# 246_PWM_PCA9685.net
KiCad netlist of a schematic drawn in EAGLE
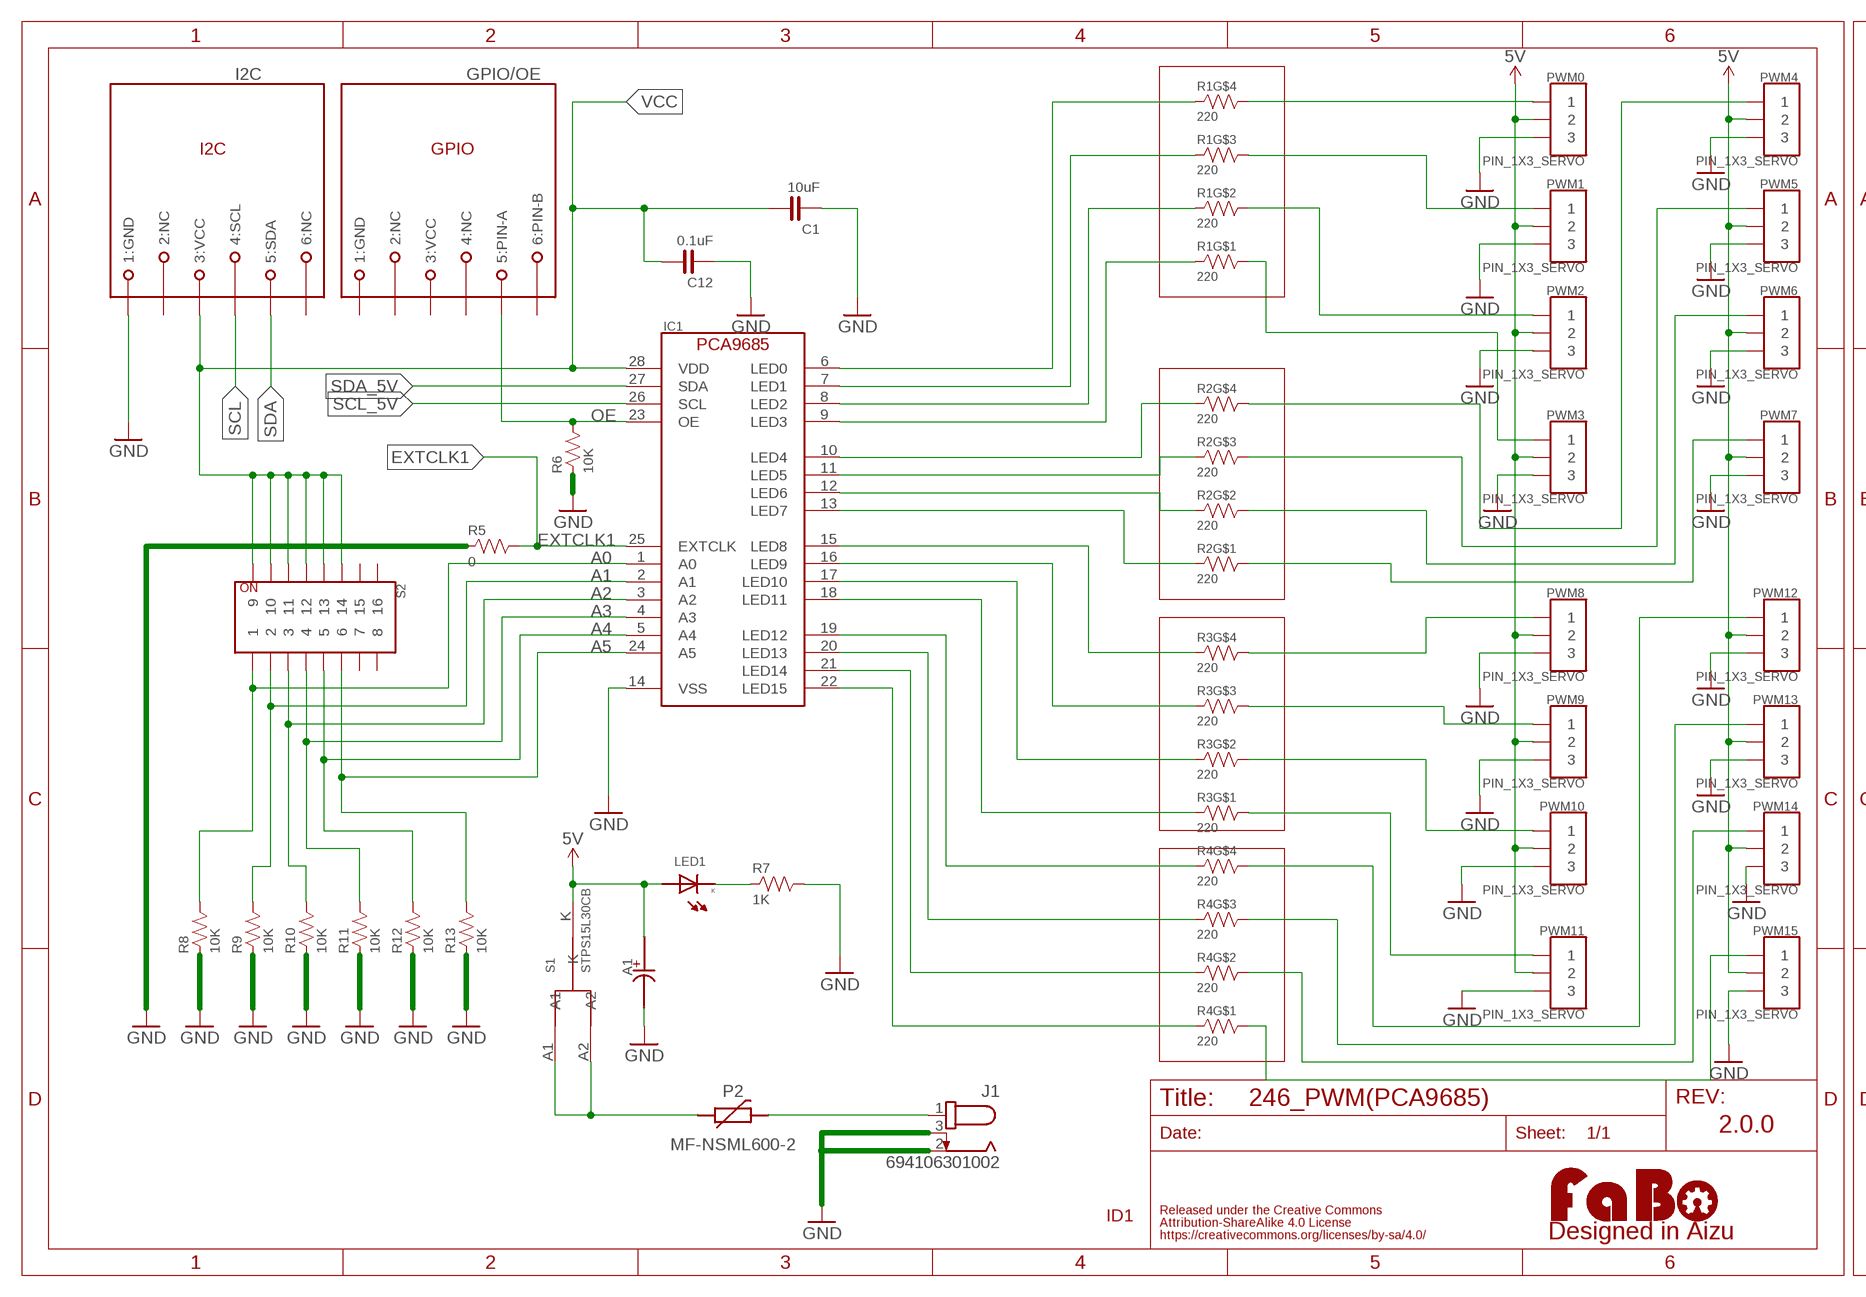
[diagram p0: schematic, sheet 1, part 1 of 2]
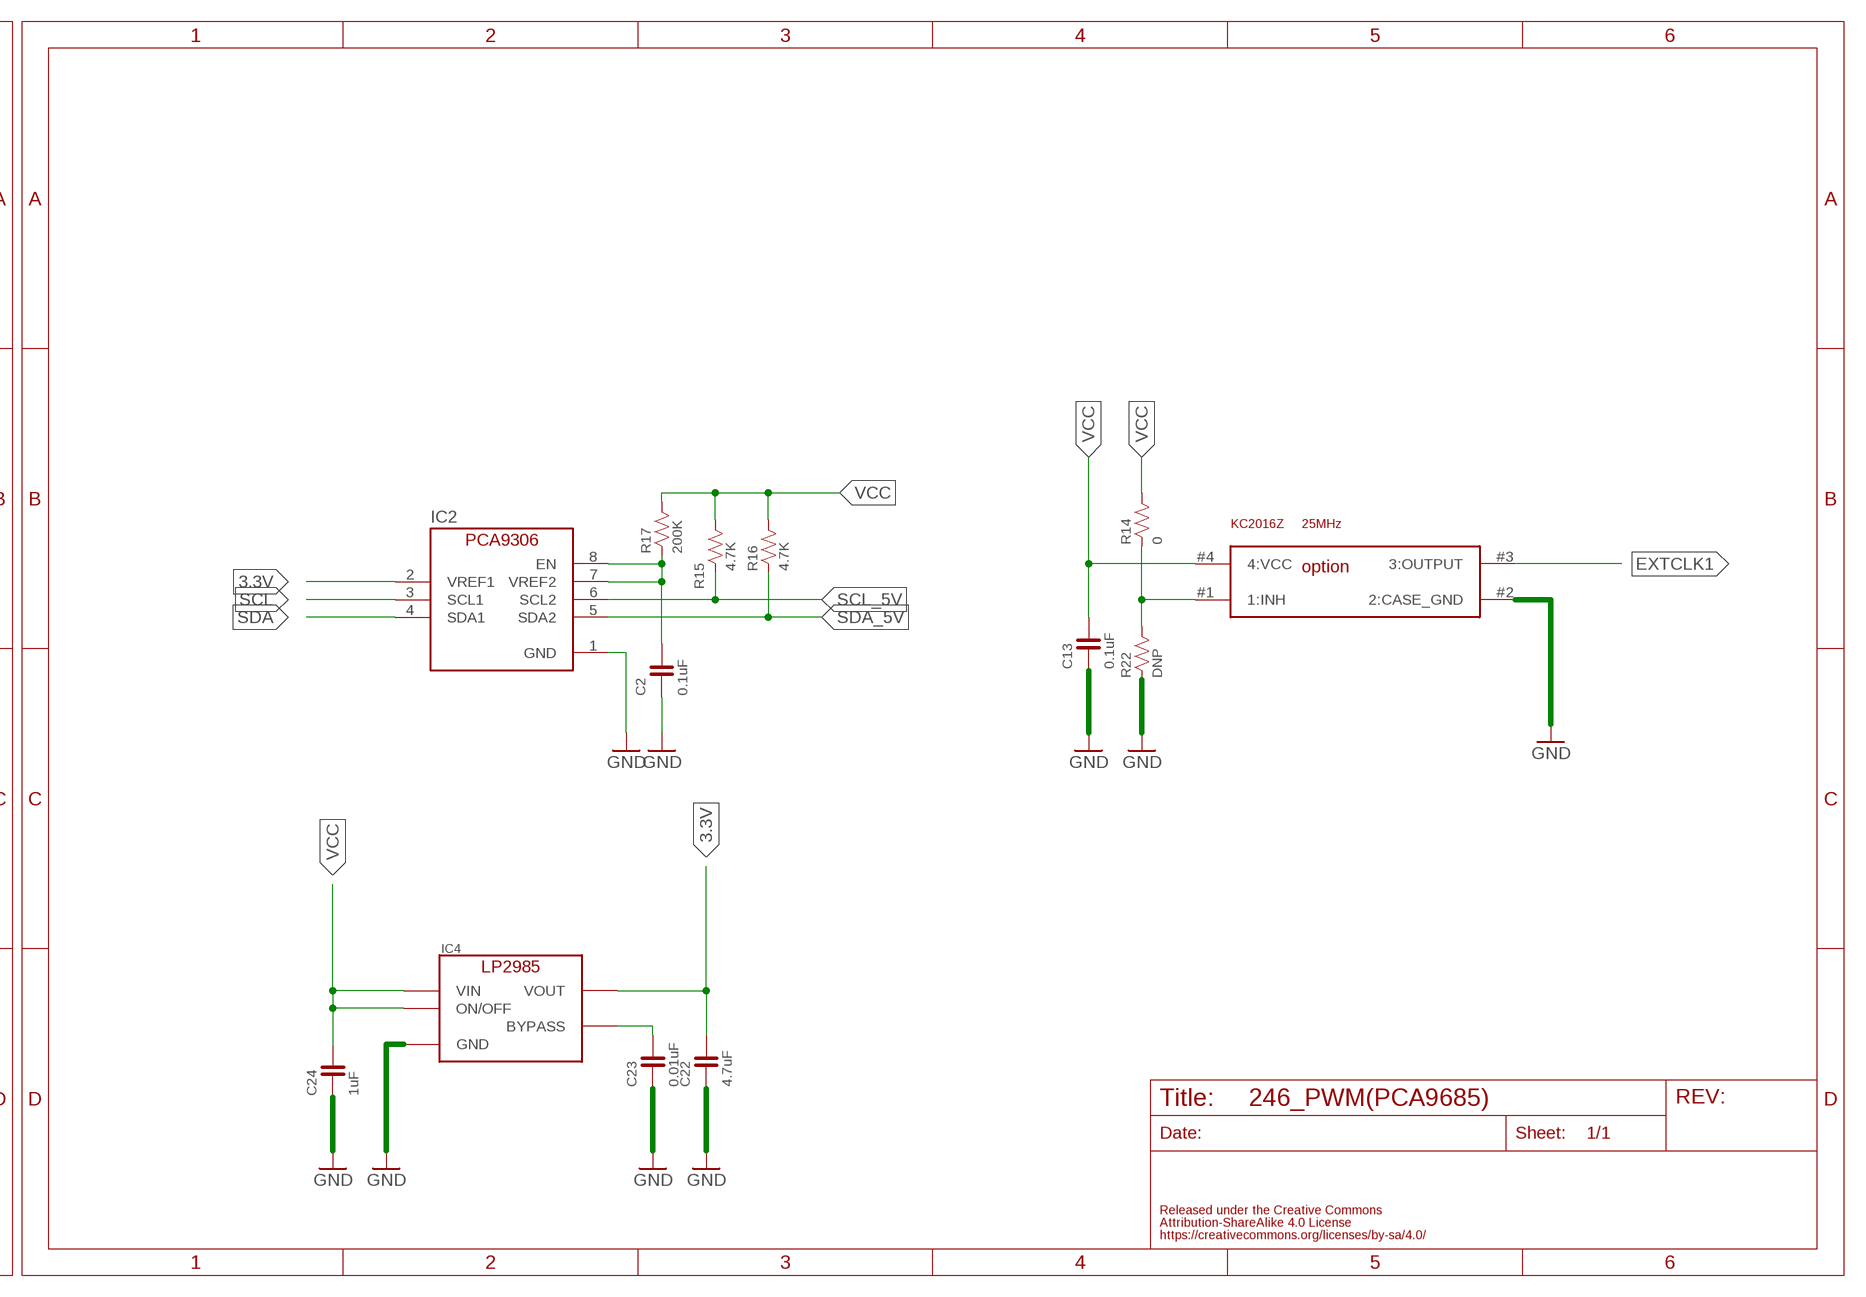
[diagram p1: schematic, sheet 1, part 2 of 2]

(export (version "E")
  (design (tool "Eeschema 10.0.6"))
  (components
    (comp (ref "A1")
      (value "CAPACITOR-OS-CON")
      (footprint "eagle-import:F13")
      (libsource (lib "eagle-import") (part "CAPACITOR-OS-CON"))
    )
    (comp (ref "C1")
      (value "10uF")
      (footprint "eagle-import:0603")
      (libsource (lib "eagle-import") (part "CAPACITOR-0603"))
    )
    (comp (ref "C2")
      (value "0.1uF")
      (footprint "eagle-import:0402")
      (libsource (lib "eagle-import") (part "CAPACITOR-0402"))
    )
    (comp (ref "C12")
      (value "0.1uF")
      (footprint "eagle-import:0603")
      (libsource (lib "eagle-import") (part "CAPACITOR-0603"))
    )
    (comp (ref "C13")
      (value "0.1uF")
      (footprint "eagle-import:0402")
      (libsource (lib "eagle-import") (part "CAPACITOR-0402"))
    )
    (comp (ref "C22")
      (value "4.7uF")
      (footprint "eagle-import:0603")
      (libsource (lib "eagle-import") (part "CAPACITOR-0603"))
    )
    (comp (ref "C23")
      (value "0.01uF")
      (footprint "eagle-import:0603")
      (libsource (lib "eagle-import") (part "CAPACITOR-0603"))
    )
    (comp (ref "C24")
      (value "1uF")
      (footprint "eagle-import:0603")
      (libsource (lib "eagle-import") (part "CAPACITOR-0603"))
    )
    (comp (ref "GPIO/OE")
      (value "MODULAR-JACK-6P-RJ11_GPIO")
      (footprint "eagle-import:7002-6PXC-X")
      (libsource (lib "eagle-import") (part "MODULAR-JACK-6P-RJ11_GPIO"))
    )
    (comp (ref "I2C")
      (value "MODULAR-JACK-6P-RJ11_I2C")
      (footprint "eagle-import:7002-6PXC-X")
      (libsource (lib "eagle-import") (part "MODULAR-JACK-6P-RJ11_I2C"))
    )
    (comp (ref "IC1")
      (value "PCA9685BS")
      (footprint "eagle-import:PCA9685")
      (libsource (lib "eagle-import") (part "PCA9685BS"))
    )
    (comp (ref "IC2")
      (value "PCA9306_GM")
      (footprint "eagle-import:XQFN8")
      (libsource (lib "eagle-import") (part "PCA9306_GM"))
    )
    (comp (ref "IC4")
      (value "LP2985-33DBV")
      (footprint "eagle-import:SOT-23-5")
      (libsource (lib "eagle-import") (part "LP2985-33DBV"))
    )
    (comp (ref "J1")
      (value "694106301002")
      (footprint "eagle-import:694106301002")
      (fields
        (field (name "DIGIKEY_PART_NUMBER") "732-5930-ND")
        (field (name "MANUFACTURER") "Wurth Electronics Inc.")
        (field (name "CREATED_BY") "PCBLayout.com")
      )
      (libsource (lib "eagle-import") (part "694106301002"))
    )
    (comp (ref "LED1")
      (value "LED-0603")
      (footprint "eagle-import:0603")
      (libsource (lib "eagle-import") (part "LED-0603"))
    )
    (comp (ref "LOGO1")
      (value "LOGO_FABO-M_BOTTOM")
      (footprint "eagle-import:LOGO_FABO_M_BOTTOM")
      (libsource (lib "eagle-import") (part "LOGO_FABO-M_BOTTOM"))
    )
    (comp (ref "P2")
      (value "MF-NSML600-2")
      (footprint "eagle-import:1206")
      (libsource (lib "eagle-import") (part "POLYSWITCH1206"))
    )
    (comp (ref "PWM0")
      (value "PIN_1X3_SERVO")
      (footprint "eagle-import:PIN_1X3_NOLABEL_PWM")
      (libsource (lib "eagle-import") (part "PIN_1X3_SERVO"))
    )
    (comp (ref "PWM1")
      (value "PIN_1X3_SERVO")
      (footprint "eagle-import:PIN_1X3_NOLABEL_PWM")
      (libsource (lib "eagle-import") (part "PIN_1X3_SERVO"))
    )
    (comp (ref "PWM2")
      (value "PIN_1X3_SERVO")
      (footprint "eagle-import:PIN_1X3_NOLABEL_PWM")
      (libsource (lib "eagle-import") (part "PIN_1X3_SERVO"))
    )
    (comp (ref "PWM3")
      (value "PIN_1X3_SERVO")
      (footprint "eagle-import:PIN_1X3_NOLABEL_PWM")
      (libsource (lib "eagle-import") (part "PIN_1X3_SERVO"))
    )
    (comp (ref "PWM4")
      (value "PIN_1X3_SERVO")
      (footprint "eagle-import:PIN_1X3_NOLABEL_PWM")
      (libsource (lib "eagle-import") (part "PIN_1X3_SERVO"))
    )
    (comp (ref "PWM5")
      (value "PIN_1X3_SERVO")
      (footprint "eagle-import:PIN_1X3_NOLABEL_PWM")
      (libsource (lib "eagle-import") (part "PIN_1X3_SERVO"))
    )
    (comp (ref "PWM6")
      (value "PIN_1X3_SERVO")
      (footprint "eagle-import:PIN_1X3_NOLABEL_PWM")
      (libsource (lib "eagle-import") (part "PIN_1X3_SERVO"))
    )
    (comp (ref "PWM7")
      (value "PIN_1X3_SERVO")
      (footprint "eagle-import:PIN_1X3_NOLABEL_PWM")
      (libsource (lib "eagle-import") (part "PIN_1X3_SERVO"))
    )
    (comp (ref "PWM8")
      (value "PIN_1X3_SERVO")
      (footprint "eagle-import:PIN_1X3_NOLABEL_PWM")
      (libsource (lib "eagle-import") (part "PIN_1X3_SERVO"))
    )
    (comp (ref "PWM9")
      (value "PIN_1X3_SERVO")
      (footprint "eagle-import:PIN_1X3_NOLABEL_PWM")
      (libsource (lib "eagle-import") (part "PIN_1X3_SERVO"))
    )
    (comp (ref "PWM10")
      (value "PIN_1X3_SERVO")
      (footprint "eagle-import:PIN_1X3_NOLABEL_PWM")
      (libsource (lib "eagle-import") (part "PIN_1X3_SERVO"))
    )
    (comp (ref "PWM11")
      (value "PIN_1X3_SERVO")
      (footprint "eagle-import:PIN_1X3_NOLABEL_PWM")
      (libsource (lib "eagle-import") (part "PIN_1X3_SERVO"))
    )
    (comp (ref "PWM12")
      (value "PIN_1X3_SERVO")
      (footprint "eagle-import:PIN_1X3_NOLABEL_PWM")
      (libsource (lib "eagle-import") (part "PIN_1X3_SERVO"))
    )
    (comp (ref "PWM13")
      (value "PIN_1X3_SERVO")
      (footprint "eagle-import:PIN_1X3_NOLABEL_PWM")
      (libsource (lib "eagle-import") (part "PIN_1X3_SERVO"))
    )
    (comp (ref "PWM14")
      (value "PIN_1X3_SERVO")
      (footprint "eagle-import:PIN_1X3_NOLABEL_PWM")
      (libsource (lib "eagle-import") (part "PIN_1X3_SERVO"))
    )
    (comp (ref "PWM15")
      (value "PIN_1X3_SERVO")
      (footprint "eagle-import:PIN_1X3_NOLABEL_PWM")
      (libsource (lib "eagle-import") (part "PIN_1X3_SERVO"))
    )
    (comp (ref "R1")
      (value "220")
      (footprint "eagle-import:EXBV8V")
      (libsource (lib "eagle-import") (part "RESISTOR_ARRAY"))
    )
    (comp (ref "R2")
      (value "220")
      (footprint "eagle-import:EXBV8V")
      (libsource (lib "eagle-import") (part "RESISTOR_ARRAY"))
    )
    (comp (ref "R3")
      (value "220")
      (footprint "eagle-import:EXBV8V")
      (libsource (lib "eagle-import") (part "RESISTOR_ARRAY"))
    )
    (comp (ref "R4")
      (value "220")
      (footprint "eagle-import:EXBV8V")
      (libsource (lib "eagle-import") (part "RESISTOR_ARRAY"))
    )
    (comp (ref "R5")
      (value "0")
      (footprint "eagle-import:0603")
      (libsource (lib "eagle-import") (part "RESISTOR-0603"))
    )
    (comp (ref "R6")
      (value "10K")
      (footprint "eagle-import:0603")
      (libsource (lib "eagle-import") (part "RESISTOR-0603"))
    )
    (comp (ref "R7")
      (value "1K")
      (footprint "eagle-import:0603")
      (libsource (lib "eagle-import") (part "RESISTOR-0603"))
    )
    (comp (ref "R8")
      (value "10K")
      (footprint "eagle-import:0603")
      (libsource (lib "eagle-import") (part "RESISTOR-0603"))
    )
    (comp (ref "R9")
      (value "10K")
      (footprint "eagle-import:0603")
      (libsource (lib "eagle-import") (part "RESISTOR-0603"))
    )
    (comp (ref "R10")
      (value "10K")
      (footprint "eagle-import:0603")
      (libsource (lib "eagle-import") (part "RESISTOR-0603"))
    )
    (comp (ref "R11")
      (value "10K")
      (footprint "eagle-import:0603")
      (libsource (lib "eagle-import") (part "RESISTOR-0603"))
    )
    (comp (ref "R12")
      (value "10K")
      (footprint "eagle-import:0603")
      (libsource (lib "eagle-import") (part "RESISTOR-0603"))
    )
    (comp (ref "R13")
      (value "10K")
      (footprint "eagle-import:0603")
      (libsource (lib "eagle-import") (part "RESISTOR-0603"))
    )
    (comp (ref "R14")
      (value "0")
      (footprint "eagle-import:0402")
      (libsource (lib "eagle-import") (part "RESISTOR-0402"))
    )
    (comp (ref "R15")
      (value "4.7K")
      (footprint "eagle-import:0402")
      (libsource (lib "eagle-import") (part "RESISTOR-0402"))
    )
    (comp (ref "R16")
      (value "4.7K")
      (footprint "eagle-import:0402")
      (libsource (lib "eagle-import") (part "RESISTOR-0402"))
    )
    (comp (ref "R17")
      (value "200K")
      (footprint "eagle-import:0402")
      (libsource (lib "eagle-import") (part "RESISTOR-0402"))
    )
    (comp (ref "R22")
      (value "DNP")
      (footprint "eagle-import:0402")
      (libsource (lib "eagle-import") (part "RESISTOR-0402"))
    )
    (comp (ref "S1")
      (value "STPS15L30CB")
      (footprint "eagle-import:STPS15L30C")
      (libsource (lib "eagle-import") (part "STPS15L30C"))
    )
    (comp (ref "S2")
      (value "KHS82")
      (footprint "eagle-import:KHS82")
      (libsource (lib "eagle-import") (part "KHS82"))
    )
    (comp (ref "U$11")
      (value "KC2016Z")
      (footprint "eagle-import:KC2016Z")
      (libsource (lib "eagle-import") (part "KC2016Z"))
    )
  )
  (nets
    (net (code "1") (name "/1:GND") (class "Default")
      (node (ref "GPIO/OE") (pin "1") (pinfunction "1:GND_1") (pintype "power_in"))
    )
    (net (code "2") (name "/3:VCC") (class "Default")
      (node (ref "GPIO/OE") (pin "3") (pinfunction "3:VCC_3") (pintype "power_in"))
    )
    (net (code "3") (name "/A0") (class "Default")
      (node (ref "IC1") (pin "1") (pinfunction "A0_1") (pintype "bidirectional"))
      (node (ref "R8") (pin "2") (pinfunction "2_2") (pintype "bidirectional"))
      (node (ref "S2") (pin "1") (pinfunction "1_1") (pintype "input"))
    )
    (net (code "4") (name "/A1") (class "Default")
      (node (ref "IC1") (pin "2") (pinfunction "A1_2") (pintype "bidirectional"))
      (node (ref "R9") (pin "2") (pinfunction "2_2") (pintype "bidirectional"))
      (node (ref "S2") (pin "2") (pinfunction "2_2") (pintype "input"))
    )
    (net (code "5") (name "/A2") (class "Default")
      (node (ref "IC1") (pin "3") (pinfunction "A2_3") (pintype "bidirectional"))
      (node (ref "R10") (pin "2") (pinfunction "2_2") (pintype "bidirectional"))
      (node (ref "S2") (pin "3") (pinfunction "3_3") (pintype "input"))
    )
    (net (code "6") (name "/A3") (class "Default")
      (node (ref "IC1") (pin "4") (pinfunction "A3_4") (pintype "bidirectional"))
      (node (ref "R11") (pin "2") (pinfunction "2_2") (pintype "bidirectional"))
      (node (ref "S2") (pin "4") (pinfunction "4_4") (pintype "input"))
    )
    (net (code "7") (name "/A4") (class "Default")
      (node (ref "IC1") (pin "5") (pinfunction "A4_5") (pintype "bidirectional"))
      (node (ref "R12") (pin "2") (pinfunction "2_2") (pintype "bidirectional"))
      (node (ref "S2") (pin "5") (pinfunction "5_5") (pintype "input"))
    )
    (net (code "8") (name "/A5") (class "Default")
      (node (ref "IC1") (pin "24") (pinfunction "A5_24") (pintype "bidirectional"))
      (node (ref "R13") (pin "2") (pinfunction "2_2") (pintype "bidirectional"))
      (node (ref "S2") (pin "6") (pinfunction "6_6") (pintype "input"))
    )
    (net (code "9") (name "/OE") (class "Default")
      (node (ref "GPIO/OE") (pin "5") (pinfunction "5:PIN-A_5") (pintype "bidirectional"))
      (node (ref "IC1") (pin "23") (pinfunction "OE_23") (pintype "bidirectional"))
      (node (ref "R6") (pin "2") (pinfunction "2_2") (pintype "bidirectional"))
    )
    (net (code "10") (name "3.3V") (class "Default")
      (node (ref "C22") (pin "2") (pinfunction "2_2") (pintype "passive"))
      (node (ref "IC2") (pin "2") (pinfunction "VREF1_2") (pintype "bidirectional"))
      (node (ref "IC4") (pin "5") (pinfunction "VOUT_5") (pintype "output"))
    )
    (net (code "11") (name "5V") (class "Default")
      (node (ref "A1") (pin "ANODE") (pinfunction "+_ANODE") (pintype "passive"))
      (node (ref "LED1") (pin "ANODE") (pinfunction "ANODE_ANODE") (pintype "passive"))
      (node (ref "PWM0") (pin "2:VCC") (pinfunction "2_2:VCC") (pintype "bidirectional"))
      (node (ref "PWM1") (pin "2:VCC") (pinfunction "2_2:VCC") (pintype "bidirectional"))
      (node (ref "PWM10") (pin "2:VCC") (pinfunction "2_2:VCC") (pintype "bidirectional"))
      (node (ref "PWM11") (pin "2:VCC") (pinfunction "2_2:VCC") (pintype "bidirectional"))
      (node (ref "PWM12") (pin "2:VCC") (pinfunction "2_2:VCC") (pintype "bidirectional"))
      (node (ref "PWM13") (pin "2:VCC") (pinfunction "2_2:VCC") (pintype "bidirectional"))
      (node (ref "PWM14") (pin "2:VCC") (pinfunction "2_2:VCC") (pintype "bidirectional"))
      (node (ref "PWM15") (pin "2:VCC") (pinfunction "2_2:VCC") (pintype "bidirectional"))
      (node (ref "PWM2") (pin "2:VCC") (pinfunction "2_2:VCC") (pintype "bidirectional"))
      (node (ref "PWM3") (pin "2:VCC") (pinfunction "2_2:VCC") (pintype "bidirectional"))
      (node (ref "PWM4") (pin "2:VCC") (pinfunction "2_2:VCC") (pintype "bidirectional"))
      (node (ref "PWM5") (pin "2:VCC") (pinfunction "2_2:VCC") (pintype "bidirectional"))
      (node (ref "PWM6") (pin "2:VCC") (pinfunction "2_2:VCC") (pintype "bidirectional"))
      (node (ref "PWM7") (pin "2:VCC") (pinfunction "2_2:VCC") (pintype "bidirectional"))
      (node (ref "PWM8") (pin "2:VCC") (pinfunction "2_2:VCC") (pintype "bidirectional"))
      (node (ref "PWM9") (pin "2:VCC") (pinfunction "2_2:VCC") (pintype "bidirectional"))
      (node (ref "S1") (pin "K") (pinfunction "K_K") (pintype "bidirectional"))
    )
    (net (code "12") (name "EXTCLK1") (class "Default")
      (node (ref "IC1") (pin "25") (pinfunction "EXTCLK_25") (pintype "bidirectional"))
      (node (ref "R5") (pin "2") (pinfunction "2_2") (pintype "bidirectional"))
      (node (ref "U$11") (pin "#3") (pinfunction "3:OUTPUT_#3") (pintype "bidirectional"))
    )
    (net (code "13") (name "GND") (class "Default")
      (node (ref "A1") (pin "CATHODE") (pinfunction "-_CATHODE") (pintype "passive"))
      (node (ref "C1") (pin "1") (pinfunction "1_1") (pintype "passive"))
      (node (ref "C12") (pin "1") (pinfunction "1_1") (pintype "passive"))
      (node (ref "C13") (pin "P$1") (pinfunction "1_P$1") (pintype "passive"))
      (node (ref "C2") (pin "P$1") (pinfunction "1_P$1") (pintype "passive"))
      (node (ref "C22") (pin "1") (pinfunction "1_1") (pintype "passive"))
      (node (ref "C23") (pin "1") (pinfunction "1_1") (pintype "passive"))
      (node (ref "C24") (pin "1") (pinfunction "1_1") (pintype "passive"))
      (node (ref "I2C") (pin "1") (pinfunction "1:GND_1") (pintype "power_in"))
      (node (ref "IC1") (pin "14") (pinfunction "VSS_14") (pintype "bidirectional"))
      (node (ref "IC2") (pin "1") (pinfunction "GND_1") (pintype "bidirectional"))
      (node (ref "IC4") (pin "2") (pinfunction "GND_2") (pintype "power_in"))
      (node (ref "J1") (pin "2") (pinfunction "2_2") (pintype "passive"))
      (node (ref "J1") (pin "3") (pinfunction "3_3") (pintype "passive"))
      (node (ref "PWM0") (pin "3:GND") (pinfunction "3_3:GND") (pintype "bidirectional"))
      (node (ref "PWM1") (pin "3:GND") (pinfunction "3_3:GND") (pintype "bidirectional"))
      (node (ref "PWM10") (pin "3:GND") (pinfunction "3_3:GND") (pintype "bidirectional"))
      (node (ref "PWM11") (pin "3:GND") (pinfunction "3_3:GND") (pintype "bidirectional"))
      (node (ref "PWM12") (pin "3:GND") (pinfunction "3_3:GND") (pintype "bidirectional"))
      (node (ref "PWM13") (pin "3:GND") (pinfunction "3_3:GND") (pintype "bidirectional"))
      (node (ref "PWM14") (pin "3:GND") (pinfunction "3_3:GND") (pintype "bidirectional"))
      (node (ref "PWM15") (pin "3:GND") (pinfunction "3_3:GND") (pintype "bidirectional"))
      (node (ref "PWM2") (pin "3:GND") (pinfunction "3_3:GND") (pintype "bidirectional"))
      (node (ref "PWM3") (pin "3:GND") (pinfunction "3_3:GND") (pintype "bidirectional"))
      (node (ref "PWM4") (pin "3:GND") (pinfunction "3_3:GND") (pintype "bidirectional"))
      (node (ref "PWM5") (pin "3:GND") (pinfunction "3_3:GND") (pintype "bidirectional"))
      (node (ref "PWM6") (pin "3:GND") (pinfunction "3_3:GND") (pintype "bidirectional"))
      (node (ref "PWM7") (pin "3:GND") (pinfunction "3_3:GND") (pintype "bidirectional"))
      (node (ref "PWM8") (pin "3:GND") (pinfunction "3_3:GND") (pintype "bidirectional"))
      (node (ref "PWM9") (pin "3:GND") (pinfunction "3_3:GND") (pintype "bidirectional"))
      (node (ref "R10") (pin "1") (pinfunction "1_1") (pintype "bidirectional"))
      (node (ref "R11") (pin "1") (pinfunction "1_1") (pintype "bidirectional"))
      (node (ref "R12") (pin "1") (pinfunction "1_1") (pintype "bidirectional"))
      (node (ref "R13") (pin "1") (pinfunction "1_1") (pintype "bidirectional"))
      (node (ref "R22") (pin "P$1") (pinfunction "1_P$1") (pintype "bidirectional"))
      (node (ref "R5") (pin "1") (pinfunction "1_1") (pintype "bidirectional"))
      (node (ref "R6") (pin "1") (pinfunction "1_1") (pintype "bidirectional"))
      (node (ref "R7") (pin "2") (pinfunction "2_2") (pintype "bidirectional"))
      (node (ref "R8") (pin "1") (pinfunction "1_1") (pintype "bidirectional"))
      (node (ref "R9") (pin "1") (pinfunction "1_1") (pintype "bidirectional"))
      (node (ref "U$11") (pin "#2") (pinfunction "2:CASE_GND_#2") (pintype "bidirectional"))
    )
    (net (code "14") (name "Net-(C2-2)") (class "Default")
      (node (ref "C2") (pin "P$2") (pinfunction "2_P$2") (pintype "passive"))
      (node (ref "IC2") (pin "7") (pinfunction "VREF2_7") (pintype "bidirectional"))
      (node (ref "IC2") (pin "8") (pinfunction "EN_8") (pintype "bidirectional"))
      (node (ref "R17") (pin "P$1") (pinfunction "1_P$1") (pintype "bidirectional"))
    )
    (net (code "15") (name "Net-(IC1-LED0)") (class "Default")
      (node (ref "IC1") (pin "6") (pinfunction "LED0_6") (pintype "bidirectional"))
      (node (ref "R1") (pin "4") (pinfunction "1_4") (pintype "bidirectional"))
    )
    (net (code "16") (name "Net-(IC1-LED1)") (class "Default")
      (node (ref "IC1") (pin "7") (pinfunction "LED1_7") (pintype "bidirectional"))
      (node (ref "R1") (pin "3") (pinfunction "1_3") (pintype "bidirectional"))
    )
    (net (code "17") (name "Net-(IC1-LED2)") (class "Default")
      (node (ref "IC1") (pin "8") (pinfunction "LED2_8") (pintype "bidirectional"))
      (node (ref "R1") (pin "2") (pinfunction "1_2") (pintype "bidirectional"))
    )
    (net (code "18") (name "Net-(IC1-LED3)") (class "Default")
      (node (ref "IC1") (pin "9") (pinfunction "LED3_9") (pintype "bidirectional"))
      (node (ref "R1") (pin "1") (pinfunction "1_1") (pintype "bidirectional"))
    )
    (net (code "19") (name "Net-(IC1-LED4)") (class "Default")
      (node (ref "IC1") (pin "10") (pinfunction "LED4_10") (pintype "bidirectional"))
      (node (ref "R2") (pin "4") (pinfunction "1_4") (pintype "bidirectional"))
    )
    (net (code "20") (name "Net-(IC1-LED5)") (class "Default")
      (node (ref "IC1") (pin "11") (pinfunction "LED5_11") (pintype "bidirectional"))
      (node (ref "R2") (pin "3") (pinfunction "1_3") (pintype "bidirectional"))
    )
    (net (code "21") (name "Net-(IC1-LED6)") (class "Default")
      (node (ref "IC1") (pin "12") (pinfunction "LED6_12") (pintype "bidirectional"))
      (node (ref "R2") (pin "2") (pinfunction "1_2") (pintype "bidirectional"))
    )
    (net (code "22") (name "Net-(IC1-LED7)") (class "Default")
      (node (ref "IC1") (pin "13") (pinfunction "LED7_13") (pintype "bidirectional"))
      (node (ref "R2") (pin "1") (pinfunction "1_1") (pintype "bidirectional"))
    )
    (net (code "23") (name "Net-(IC1-LED8)") (class "Default")
      (node (ref "IC1") (pin "15") (pinfunction "LED8_15") (pintype "bidirectional"))
      (node (ref "R3") (pin "4") (pinfunction "1_4") (pintype "bidirectional"))
    )
    (net (code "24") (name "Net-(IC1-LED9)") (class "Default")
      (node (ref "IC1") (pin "16") (pinfunction "LED9_16") (pintype "bidirectional"))
      (node (ref "R3") (pin "3") (pinfunction "1_3") (pintype "bidirectional"))
    )
    (net (code "25") (name "Net-(IC1-LED10)") (class "Default")
      (node (ref "IC1") (pin "17") (pinfunction "LED10_17") (pintype "bidirectional"))
      (node (ref "R3") (pin "2") (pinfunction "1_2") (pintype "bidirectional"))
    )
    (net (code "26") (name "Net-(IC1-LED11)") (class "Default")
      (node (ref "IC1") (pin "18") (pinfunction "LED11_18") (pintype "bidirectional"))
      (node (ref "R3") (pin "1") (pinfunction "1_1") (pintype "bidirectional"))
    )
    (net (code "27") (name "Net-(IC1-LED12)") (class "Default")
      (node (ref "IC1") (pin "19") (pinfunction "LED12_19") (pintype "bidirectional"))
      (node (ref "R4") (pin "4") (pinfunction "1_4") (pintype "bidirectional"))
    )
    (net (code "28") (name "Net-(IC1-LED13)") (class "Default")
      (node (ref "IC1") (pin "20") (pinfunction "LED13_20") (pintype "bidirectional"))
      (node (ref "R4") (pin "3") (pinfunction "1_3") (pintype "bidirectional"))
    )
    (net (code "29") (name "Net-(IC1-LED14)") (class "Default")
      (node (ref "IC1") (pin "21") (pinfunction "LED14_21") (pintype "bidirectional"))
      (node (ref "R4") (pin "2") (pinfunction "1_2") (pintype "bidirectional"))
    )
    (net (code "30") (name "Net-(IC1-LED15)") (class "Default")
      (node (ref "IC1") (pin "22") (pinfunction "LED15_22") (pintype "bidirectional"))
      (node (ref "R4") (pin "1") (pinfunction "1_1") (pintype "bidirectional"))
    )
    (net (code "31") (name "Net-(IC4-BYPASS)") (class "Default")
      (node (ref "C23") (pin "2") (pinfunction "2_2") (pintype "passive"))
      (node (ref "IC4") (pin "4") (pinfunction "BYPASS_4") (pintype "bidirectional"))
    )
    (net (code "32") (name "Net-(LED1-PadCATHODE)") (class "Default")
      (node (ref "LED1") (pin "CATHODE") (pinfunction "CATHODE_CATHODE") (pintype "passive"))
      (node (ref "R7") (pin "1") (pinfunction "1_1") (pintype "bidirectional"))
    )
    (net (code "33") (name "Net-(P2-1)") (class "Default")
      (node (ref "P2") (pin "P$1") (pinfunction "1_P$1") (pintype "bidirectional"))
      (node (ref "S1") (pin "A1") (pinfunction "A1_A1") (pintype "bidirectional"))
      (node (ref "S1") (pin "A2") (pinfunction "A2_A2") (pintype "bidirectional"))
    )
    (net (code "34") (name "Net-(P2-2)") (class "Default")
      (node (ref "J1") (pin "1") (pinfunction "1_1") (pintype "passive"))
      (node (ref "P2") (pin "P$2") (pinfunction "2_P$2") (pintype "bidirectional"))
    )
    (net (code "35") (name "Net-(PWM0-1)") (class "Default")
      (node (ref "PWM0") (pin "1:SIGNAL") (pinfunction "1_1:SIGNAL") (pintype "bidirectional"))
      (node (ref "R1") (pin "5") (pinfunction "2_5") (pintype "bidirectional"))
    )
    (net (code "36") (name "Net-(PWM1-1)") (class "Default")
      (node (ref "PWM1") (pin "1:SIGNAL") (pinfunction "1_1:SIGNAL") (pintype "bidirectional"))
      (node (ref "R1") (pin "6") (pinfunction "2_6") (pintype "bidirectional"))
    )
    (net (code "37") (name "Net-(PWM2-1)") (class "Default")
      (node (ref "PWM2") (pin "1:SIGNAL") (pinfunction "1_1:SIGNAL") (pintype "bidirectional"))
      (node (ref "R1") (pin "7") (pinfunction "2_7") (pintype "bidirectional"))
    )
    (net (code "38") (name "Net-(PWM3-1)") (class "Default")
      (node (ref "PWM3") (pin "1:SIGNAL") (pinfunction "1_1:SIGNAL") (pintype "bidirectional"))
      (node (ref "R1") (pin "8") (pinfunction "2_8") (pintype "bidirectional"))
    )
    (net (code "39") (name "Net-(PWM4-1)") (class "Default")
      (node (ref "PWM4") (pin "1:SIGNAL") (pinfunction "1_1:SIGNAL") (pintype "bidirectional"))
      (node (ref "R2") (pin "5") (pinfunction "2_5") (pintype "bidirectional"))
    )
    (net (code "40") (name "Net-(PWM5-1)") (class "Default")
      (node (ref "PWM5") (pin "1:SIGNAL") (pinfunction "1_1:SIGNAL") (pintype "bidirectional"))
      (node (ref "R2") (pin "6") (pinfunction "2_6") (pintype "bidirectional"))
    )
    (net (code "41") (name "Net-(PWM6-1)") (class "Default")
      (node (ref "PWM6") (pin "1:SIGNAL") (pinfunction "1_1:SIGNAL") (pintype "bidirectional"))
      (node (ref "R2") (pin "7") (pinfunction "2_7") (pintype "bidirectional"))
    )
    (net (code "42") (name "Net-(PWM7-1)") (class "Default")
      (node (ref "PWM7") (pin "1:SIGNAL") (pinfunction "1_1:SIGNAL") (pintype "bidirectional"))
      (node (ref "R2") (pin "8") (pinfunction "2_8") (pintype "bidirectional"))
    )
    (net (code "43") (name "Net-(PWM8-1)") (class "Default")
      (node (ref "PWM8") (pin "1:SIGNAL") (pinfunction "1_1:SIGNAL") (pintype "bidirectional"))
      (node (ref "R3") (pin "5") (pinfunction "2_5") (pintype "bidirectional"))
    )
    (net (code "44") (name "Net-(PWM9-1)") (class "Default")
      (node (ref "PWM9") (pin "1:SIGNAL") (pinfunction "1_1:SIGNAL") (pintype "bidirectional"))
      (node (ref "R3") (pin "6") (pinfunction "2_6") (pintype "bidirectional"))
    )
    (net (code "45") (name "Net-(PWM10-1)") (class "Default")
      (node (ref "PWM10") (pin "1:SIGNAL") (pinfunction "1_1:SIGNAL") (pintype "bidirectional"))
      (node (ref "R3") (pin "7") (pinfunction "2_7") (pintype "bidirectional"))
    )
    (net (code "46") (name "Net-(PWM11-1)") (class "Default")
      (node (ref "PWM11") (pin "1:SIGNAL") (pinfunction "1_1:SIGNAL") (pintype "bidirectional"))
      (node (ref "R3") (pin "8") (pinfunction "2_8") (pintype "bidirectional"))
    )
    (net (code "47") (name "Net-(PWM12-1)") (class "Default")
      (node (ref "PWM12") (pin "1:SIGNAL") (pinfunction "1_1:SIGNAL") (pintype "bidirectional"))
      (node (ref "R4") (pin "5") (pinfunction "2_5") (pintype "bidirectional"))
    )
    (net (code "48") (name "Net-(PWM13-1)") (class "Default")
      (node (ref "PWM13") (pin "1:SIGNAL") (pinfunction "1_1:SIGNAL") (pintype "bidirectional"))
      (node (ref "R4") (pin "6") (pinfunction "2_6") (pintype "bidirectional"))
    )
    (net (code "49") (name "Net-(PWM14-1)") (class "Default")
      (node (ref "PWM14") (pin "1:SIGNAL") (pinfunction "1_1:SIGNAL") (pintype "bidirectional"))
      (node (ref "R4") (pin "7") (pinfunction "2_7") (pintype "bidirectional"))
    )
    (net (code "50") (name "Net-(PWM15-1)") (class "Default")
      (node (ref "PWM15") (pin "1:SIGNAL") (pinfunction "1_1:SIGNAL") (pintype "bidirectional"))
      (node (ref "R4") (pin "8") (pinfunction "2_8") (pintype "bidirectional"))
    )
    (net (code "51") (name "Net-(R14-1)") (class "Default")
      (node (ref "R14") (pin "P$1") (pinfunction "1_P$1") (pintype "bidirectional"))
      (node (ref "R22") (pin "P$2") (pinfunction "2_P$2") (pintype "bidirectional"))
      (node (ref "U$11") (pin "#1") (pinfunction "1:INH_#1") (pintype "bidirectional"))
    )
    (net (code "52") (name "SCL") (class "Default")
      (node (ref "I2C") (pin "4") (pinfunction "4:SCL_4") (pintype "open_collector"))
      (node (ref "IC2") (pin "3") (pinfunction "SCL1_3") (pintype "bidirectional"))
    )
    (net (code "53") (name "SCL_5V") (class "Default")
      (node (ref "IC1") (pin "26") (pinfunction "SCL_26") (pintype "bidirectional"))
      (node (ref "IC2") (pin "6") (pinfunction "SCL2_6") (pintype "bidirectional"))
      (node (ref "R15") (pin "P$1") (pinfunction "1_P$1") (pintype "bidirectional"))
    )
    (net (code "54") (name "SDA") (class "Default")
      (node (ref "I2C") (pin "5") (pinfunction "5:SDA_5") (pintype "open_collector"))
      (node (ref "IC2") (pin "4") (pinfunction "SDA1_4") (pintype "bidirectional"))
    )
    (net (code "55") (name "SDA_5V") (class "Default")
      (node (ref "IC1") (pin "27") (pinfunction "SDA_27") (pintype "bidirectional"))
      (node (ref "IC2") (pin "5") (pinfunction "SDA2_5") (pintype "bidirectional"))
      (node (ref "R16") (pin "P$1") (pinfunction "1_P$1") (pintype "bidirectional"))
    )
    (net (code "56") (name "VCC") (class "Default")
      (node (ref "C1") (pin "2") (pinfunction "2_2") (pintype "passive"))
      (node (ref "C12") (pin "2") (pinfunction "2_2") (pintype "passive"))
      (node (ref "C13") (pin "P$2") (pinfunction "2_P$2") (pintype "passive"))
      (node (ref "C24") (pin "2") (pinfunction "2_2") (pintype "passive"))
      (node (ref "I2C") (pin "3") (pinfunction "3:VCC_3") (pintype "power_in"))
      (node (ref "IC1") (pin "28") (pinfunction "VDD_28") (pintype "bidirectional"))
      (node (ref "IC4") (pin "1") (pinfunction "VIN_1") (pintype "input"))
      (node (ref "IC4") (pin "3") (pinfunction "ON/OFF_3") (pintype "input"))
      (node (ref "R14") (pin "P$2") (pinfunction "2_P$2") (pintype "bidirectional"))
      (node (ref "R15") (pin "P$2") (pinfunction "2_P$2") (pintype "bidirectional"))
      (node (ref "R16") (pin "P$2") (pinfunction "2_P$2") (pintype "bidirectional"))
      (node (ref "R17") (pin "P$2") (pinfunction "2_P$2") (pintype "bidirectional"))
      (node (ref "S2") (pin "10") (pinfunction "10_10") (pintype "bidirectional"))
      (node (ref "S2") (pin "11") (pinfunction "11_11") (pintype "bidirectional"))
      (node (ref "S2") (pin "12") (pinfunction "12_12") (pintype "bidirectional"))
      (node (ref "S2") (pin "13") (pinfunction "13_13") (pintype "bidirectional"))
      (node (ref "S2") (pin "14") (pinfunction "14_14") (pintype "bidirectional"))
      (node (ref "S2") (pin "9") (pinfunction "9_9") (pintype "bidirectional"))
      (node (ref "U$11") (pin "#4") (pinfunction "4:VCC_#4") (pintype "bidirectional"))
    )
    (net (code "57") (name "unconnected-(GPIO/OE-2:NC-Pad2)") (class "Default")
      (node (ref "GPIO/OE") (pin "2") (pinfunction "2:NC_2") (pintype "no_connect"))
    )
    (net (code "58") (name "unconnected-(GPIO/OE-4:NC-Pad4)") (class "Default")
      (node (ref "GPIO/OE") (pin "4") (pinfunction "4:NC_4") (pintype "no_connect"))
    )
    (net (code "59") (name "unconnected-(GPIO/OE-6:PIN-B-Pad6)") (class "Default")
      (node (ref "GPIO/OE") (pin "6") (pinfunction "6:PIN-B_6") (pintype "bidirectional"))
    )
    (net (code "60") (name "unconnected-(I2C-2:NC-Pad2)") (class "Default")
      (node (ref "I2C") (pin "2") (pinfunction "2:NC_2") (pintype "no_connect"))
    )
    (net (code "61") (name "unconnected-(I2C-6:NC-Pad6)") (class "Default")
      (node (ref "I2C") (pin "6") (pinfunction "6:NC_6") (pintype "no_connect"))
    )
    (net (code "62") (name "unconnected-(S2-Pad7)") (class "Default")
      (node (ref "S2") (pin "7") (pinfunction "7_7") (pintype "input"))
    )
    (net (code "63") (name "unconnected-(S2-Pad8)") (class "Default")
      (node (ref "S2") (pin "8") (pinfunction "8_8") (pintype "input"))
    )
    (net (code "64") (name "unconnected-(S2-Pad15)") (class "Default")
      (node (ref "S2") (pin "15") (pinfunction "15_15") (pintype "bidirectional"))
    )
    (net (code "65") (name "unconnected-(S2-Pad16)") (class "Default")
      (node (ref "S2") (pin "16") (pinfunction "16_16") (pintype "bidirectional"))
    )
  )
)
